# 01_Power.net
KiCad netlist of a schematic drawn in Altium Designer
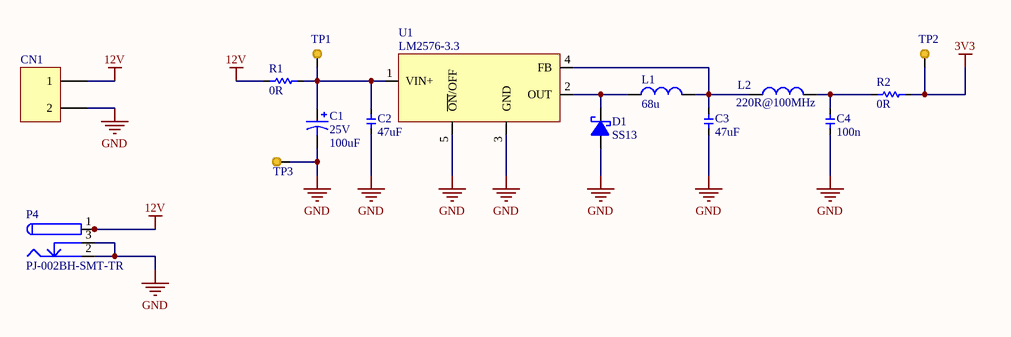
[diagram p0: 01_Power.SchDoc]

(export (version "E")
  (design (tool "Eeschema 10.0.6"))
  (components
    (comp (ref "C1")
      (value "25V")
      (footprint "Moji Footprintovi:Electrolytic Cap 2.54mm")
      (description "CAP ALUM 100UF 20% 25V RADIAL")
      (fields
        (field (name "MANUFACTURER") "Nichicon")
        (field (name "MANUFACTURER PART NUMBER") "UHE1E101MED")
        (field (name "ALTIUM_VALUE") "100uF")
      )
      (libsource (lib "Moji Schematici") (part "Cap Electrolytic"))
    )
    (comp (ref "C2")
      (value "47uF")
      (footprint "Moji Footprintovi:CAPC_1411_3528_X08N")
      (description "CAP TANT POLY47UF 20% 16V 1210")
      (fields
        (field (name "MANUFACTURER") "AVX Corporation")
        (field (name "MANUFACTURER PART NUMBER") "TCNT476M016R0200A")
      )
      (libsource (lib "Moji Schematici") (part "Cap"))
    )
    (comp (ref "C3")
      (value "47uF")
      (footprint "Moji Footprintovi:CAPC_1411_3528_X08N")
      (description "CAP TANT POLY47UF 20% 16V 1210")
      (fields
        (field (name "MANUFACTURER") "AVX Corporation")
        (field (name "MANUFACTURER PART NUMBER") "TCNT476M016R0200A")
      )
      (libsource (lib "Moji Schematici") (part "Cap"))
    )
    (comp (ref "C4")
      (value "100n")
      (footprint "Moji Footprintovi:0603 - CAP")
      (description "Capacitor")
      (fields
        (field (name "MANUFACTURER") "AVX Corporation")
        (field (name "MANUFACTURER PART NUMBER") "06035C104KAT2A")
      )
      (libsource (lib "Moji Schematici") (part "Cap"))
    )
    (comp (ref "CN1")
      (value "Terminal 2 - 5mm")
      (footprint "Moji Footprintovi:Terminal 2")
      (description "TERM BLOCK PCB 2POS 5.0MM GREEN")
      (fields
        (field (name "MANUFACTURER") "Phoenix Contact")
        (field (name "MANUFACTURER PART NUMBER") "1935161")
      )
      (libsource (lib "Moji Schematici") (part "Terminal 2"))
    )
    (comp (ref "D1")
      (value "SS13")
      (footprint "Moji Footprintovi:SOD123F")
      (description "DIODE SCHOTTKY 30V 1A SMA")
      (fields
        (field (name "MANUFACTURER") "ON Semiconductor")
        (field (name "DISTRIBUTOR PART NUMBER") "SS13FSCT-ND")
      )
      (libsource (lib "Moji Schematici") (part "Diode Schotky"))
    )
    (comp (ref "L1")
      (value "68u")
      (footprint "Moji Footprintovi:IND_TH_SMD")
      (description "FIXED IND 68UH 1A 289 MOHM SMD")
      (fields
        (field (name "MANUFACTURER") "Laird-Signal Integrity Products")
        (field (name "MANUFACTURER PART NUMBER") "TYS6045680M-10")
      )
      (libsource (lib "Moji Schematici") (part "Inductor"))
    )
    (comp (ref "L2")
      (value "220R@100MHz")
      (footprint "Moji Footprintovi:0603")
      (description "FERRITE BEAD 220 OHM 0603 1LN")
      (fields
        (field (name "MANUFACTURER") "Murata Electronics North America")
        (field (name "MANUFACTURER PART NUMBER") "BLM18KG221SN1D")
      )
      (libsource (lib "Moji Schematici") (part "Inductor"))
    )
    (comp (ref "P4")
      (value "PJ-002BH-SMT-TR")
      (footprint "Moji Footprintovi:PJ-002BH-SMT-TR")
      (description "CONN PWR JACK 2.5X5.5MM SOLDER")
      (fields
        (field (name "MANUFACTURER") "CUI Inc.")
        (field (name "DISTRIBUTOR PART NUMBER") "CP-002BHPJCT-ND")
      )
      (libsource (lib "Moji Schematici") (part "DC Jack 2.5mm - Male"))
    )
    (comp (ref "R1")
      (value "0R")
      (footprint "Moji Footprintovi:0603")
      (description "Resistor")
      (fields
        (field (name "MANUFACTURER") "Yageo")
        (field (name "MANUFACTURER PART NUMBER") "RC0603JR-070RL")
      )
      (libsource (lib "Moji Schematici") (part "Res"))
    )
    (comp (ref "R2")
      (value "0R")
      (footprint "Moji Footprintovi:0603")
      (description "Resistor")
      (fields
        (field (name "MANUFACTURER") "Yageo")
        (field (name "MANUFACTURER PART NUMBER") "RC0603JR-070RL")
      )
      (libsource (lib "Moji Schematici") (part "Res"))
    )
    (comp (ref "TP1")
      (value "Test Point 0.6mm")
      (footprint "Moji Footprintovi:TP_SMD_1mm")
      (libsource (lib "Moji Schematici") (part "TP"))
    )
    (comp (ref "TP2")
      (value "Test Point 0.6mm")
      (footprint "Moji Footprintovi:TP_SMD_1mm")
      (libsource (lib "Moji Schematici") (part "TP"))
    )
    (comp (ref "TP3")
      (value "Test Point 0.6mm")
      (footprint "Moji Footprintovi:TP_SMD_1mm")
      (libsource (lib "Moji Schematici") (part "TP"))
    )
    (comp (ref "U1")
      (value "LM2576-3.3")
      (footprint "Moji Footprintovi:TO263-5")
      (description "Switching mode regulator [ 3v3, 5v, 12v and ADJ ]")
      (fields
        (field (name "DISTRIBUTOR PART NUMBER") "LM2576-3.3WU-ND")
        (field (name "MANUFACTURER") "Microchip Technology")
      )
      (libsource (lib "Moji Schematici") (part "LM2576-xx"))
    )
  )
  (nets
    (net (code "1") (name "3V3") (class "Default")
      (node (ref "R2") (pin "1") (pinfunction "1_1") (pintype "passive"))
      (node (ref "TP2") (pin "1") (pinfunction "1_1") (pintype "passive"))
    )
    (net (code "2") (name "12V") (class "Default")
      (node (ref "CN1") (pin "1") (pinfunction "1_1") (pintype "passive"))
      (node (ref "P4") (pin "1") (pinfunction "1_1") (pintype "power_in"))
      (node (ref "P4") (pin "1A") (pinfunction "1_1A") (pintype "power_in"))
      (node (ref "R1") (pin "2") (pinfunction "2_2") (pintype "passive"))
    )
    (net (code "3") (name "GND") (class "Default")
      (node (ref "C1") (pin "2") (pinfunction "2_2") (pintype "passive"))
      (node (ref "C2") (pin "1") (pinfunction "1_1") (pintype "passive"))
      (node (ref "C3") (pin "1") (pinfunction "1_1") (pintype "passive"))
      (node (ref "C4") (pin "1") (pinfunction "1_1") (pintype "passive"))
      (node (ref "CN1") (pin "2") (pinfunction "2_2") (pintype "passive"))
      (node (ref "D1") (pin "A") (pinfunction "A_A") (pintype "passive"))
      (node (ref "P4") (pin "2") (pinfunction "2_2") (pintype "power_in"))
      (node (ref "P4") (pin "3") (pinfunction "3_3") (pintype "power_in"))
      (node (ref "TP3") (pin "1") (pinfunction "1_1") (pintype "passive"))
      (node (ref "U1") (pin "3") (pinfunction "GND_3") (pintype "passive"))
      (node (ref "U1") (pin "5") (pinfunction "~{ON}/OFF_5") (pintype "passive"))
    )
    (net (code "4") (name "Net-(C4-Pad2)") (class "Default")
      (node (ref "C4") (pin "2") (pinfunction "2_2") (pintype "passive"))
      (node (ref "L2") (pin "2") (pinfunction "2_2") (pintype "passive"))
      (node (ref "R2") (pin "2") (pinfunction "2_2") (pintype "passive"))
    )
    (net (code "5") (name "Net-(U1-FB)") (class "Default")
      (node (ref "C3") (pin "2") (pinfunction "2_2") (pintype "passive"))
      (node (ref "L1") (pin "2") (pinfunction "2_2") (pintype "passive"))
      (node (ref "L2") (pin "1") (pinfunction "1_1") (pintype "passive"))
      (node (ref "U1") (pin "4") (pinfunction "FB_4") (pintype "passive"))
    )
    (net (code "6") (name "Net-(U1-OUT)") (class "Default")
      (node (ref "D1") (pin "K") (pinfunction "K_K") (pintype "passive"))
      (node (ref "L1") (pin "1") (pinfunction "1_1") (pintype "passive"))
      (node (ref "U1") (pin "2") (pinfunction "OUT_2") (pintype "passive"))
    )
    (net (code "7") (name "Net-(U1-VIN+)") (class "Default")
      (node (ref "C1") (pin "1") (pinfunction "1_1") (pintype "passive"))
      (node (ref "C2") (pin "2") (pinfunction "2_2") (pintype "passive"))
      (node (ref "R1") (pin "1") (pinfunction "1_1") (pintype "passive"))
      (node (ref "TP1") (pin "1") (pinfunction "1_1") (pintype "passive"))
      (node (ref "U1") (pin "1") (pinfunction "VIN+_1") (pintype "passive"))
    )
  )
)
